# Puzzle_-_Collision_Sensor_V0_9b.net
KiCad netlist of a schematic drawn in EAGLE
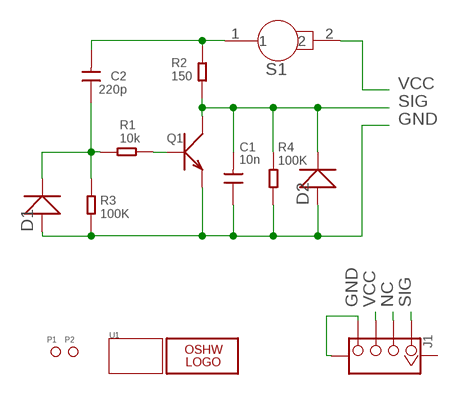
[diagram p0: schematic, sheet 1]

(export (version "E")
  (design (tool "Eeschema 10.0.6"))
  (components
    (comp (ref "C1")
      (value "10n")
      (footprint "eagle-import:0603")
      (libsource (lib "eagle-import") (part "C-0603"))
    )
    (comp (ref "C2")
      (value "220p")
      (footprint "eagle-import:0603")
      (libsource (lib "eagle-import") (part "C-0603"))
    )
    (comp (ref "D1")
      (value "D1N4148-SMD")
      (footprint "eagle-import:DO-35-SMD")
      (libsource (lib "eagle-import") (part "D1N4148-SMD"))
    )
    (comp (ref "D2")
      (value "D1N4148-SMD")
      (footprint "eagle-import:DO-35-SMD")
      (libsource (lib "eagle-import") (part "D1N4148-SMD"))
    )
    (comp (ref "J1")
      (value "TWIG-4P-2.0-SMD-FEMALE-REINFORCE'DD'")
      (footprint "eagle-import:4P-SMD-2.0")
      (libsource (lib "eagle-import") (part "TWIG-4P-2.0-SMD-FEMALE-REINFORCE'DD'"))
    )
    (comp (ref "LOGO1")
      (value "LOGO-OSHW-6MILX0200-NT")
      (footprint "eagle-import:OSHW_6X200_NOTEXT")
      (libsource (lib "eagle-import") (part "LOGO-OSHW-6MILX0200-NT"))
    )
    (comp (ref "P1")
      (value "PAD-MARK")
      (footprint "eagle-import:ROUND-MARK-0.635")
      (libsource (lib "eagle-import") (part "PAD-MARK"))
    )
    (comp (ref "P2")
      (value "PAD-MARK")
      (footprint "eagle-import:ROUND-MARK-0.635")
      (libsource (lib "eagle-import") (part "PAD-MARK"))
    )
    (comp (ref "Q1")
      (value "TRANSISTOR-NPN-SOT23''")
      (footprint "eagle-import:SOT23")
      (libsource (lib "eagle-import") (part "TRANSISTOR-NPN-SOT23''"))
    )
    (comp (ref "R1")
      (value "10k")
      (footprint "eagle-import:0603")
      (libsource (lib "eagle-import") (part "R-0603"))
    )
    (comp (ref "R2")
      (value "150")
      (footprint "eagle-import:0603")
      (libsource (lib "eagle-import") (part "R-0603"))
    )
    (comp (ref "R3")
      (value "100K")
      (footprint "eagle-import:0603")
      (libsource (lib "eagle-import") (part "R-0603"))
    )
    (comp (ref "R4")
      (value "100K")
      (footprint "eagle-import:0603")
      (libsource (lib "eagle-import") (part "R-0603"))
    )
    (comp (ref "S1")
      (value "SENSOR-COLLISION")
      (footprint "eagle-import:2P-ROUND-D5.4MM")
      (libsource (lib "eagle-import") (part "SENSOR-COLLISION"))
    )
    (comp (ref "U1")
      (value "TWIG-1U")
      (footprint "eagle-import:1U-DIM-W_-DRILL")
      (libsource (lib "eagle-import") (part "TWIG-1U"))
    )
  )
  (nets
    (net (code "1") (name "/GND") (class "Default")
      (node (ref "C1") (pin "1") (pinfunction "1_1") (pintype "passive"))
      (node (ref "D1") (pin "A") (pinfunction "+_A") (pintype "passive"))
      (node (ref "D2") (pin "A") (pinfunction "+_A") (pintype "passive"))
      (node (ref "J1") (pin "4") (pinfunction "4_4") (pintype "bidirectional"))
      (node (ref "J1") (pin "SS2") (pinfunction "SS2_SS2") (pintype "bidirectional"))
      (node (ref "Q1") (pin "2") (pinfunction "E_2") (pintype "passive"))
      (node (ref "R3") (pin "2") (pinfunction "2_2") (pintype "passive"))
      (node (ref "R4") (pin "2") (pinfunction "2_2") (pintype "passive"))
    )
    (net (code "2") (name "/NC") (class "Default")
      (node (ref "J1") (pin "2") (pinfunction "2_2") (pintype "bidirectional"))
    )
    (net (code "3") (name "/SIG") (class "Default")
      (node (ref "C1") (pin "2") (pinfunction "2_2") (pintype "passive"))
      (node (ref "D2") (pin "C") (pinfunction "-_C") (pintype "passive"))
      (node (ref "J1") (pin "1") (pinfunction "1_1") (pintype "bidirectional"))
      (node (ref "Q1") (pin "3") (pinfunction "C_3") (pintype "passive"))
      (node (ref "R2") (pin "2") (pinfunction "2_2") (pintype "passive"))
      (node (ref "R4") (pin "1") (pinfunction "1_1") (pintype "passive"))
    )
    (net (code "4") (name "/VCC") (class "Default")
      (node (ref "J1") (pin "3") (pinfunction "3_3") (pintype "bidirectional"))
      (node (ref "S1") (pin "2") (pinfunction "2_2") (pintype "bidirectional"))
    )
    (net (code "5") (name "Net-(C2-Pad2)") (class "Default")
      (node (ref "C2") (pin "2") (pinfunction "2_2") (pintype "passive"))
      (node (ref "R2") (pin "1") (pinfunction "1_1") (pintype "passive"))
      (node (ref "S1") (pin "1") (pinfunction "1_1") (pintype "bidirectional"))
    )
    (net (code "6") (name "Net-(D1--)") (class "Default")
      (node (ref "C2") (pin "1") (pinfunction "1_1") (pintype "passive"))
      (node (ref "D1") (pin "C") (pinfunction "-_C") (pintype "passive"))
      (node (ref "R1") (pin "2") (pinfunction "2_2") (pintype "passive"))
      (node (ref "R3") (pin "1") (pinfunction "1_1") (pintype "passive"))
    )
    (net (code "7") (name "Net-(Q1-B)") (class "Default")
      (node (ref "Q1") (pin "1") (pinfunction "B_1") (pintype "passive"))
      (node (ref "R1") (pin "1") (pinfunction "1_1") (pintype "passive"))
    )
    (net (code "8") (name "unconnected-(J1-PadSS1)") (class "Default")
      (node (ref "J1") (pin "SS1") (pinfunction "SS1_SS1") (pintype "bidirectional"))
    )
  )
)
